# BaseBoard.net
KiCad netlist of a schematic drawn in EAGLE
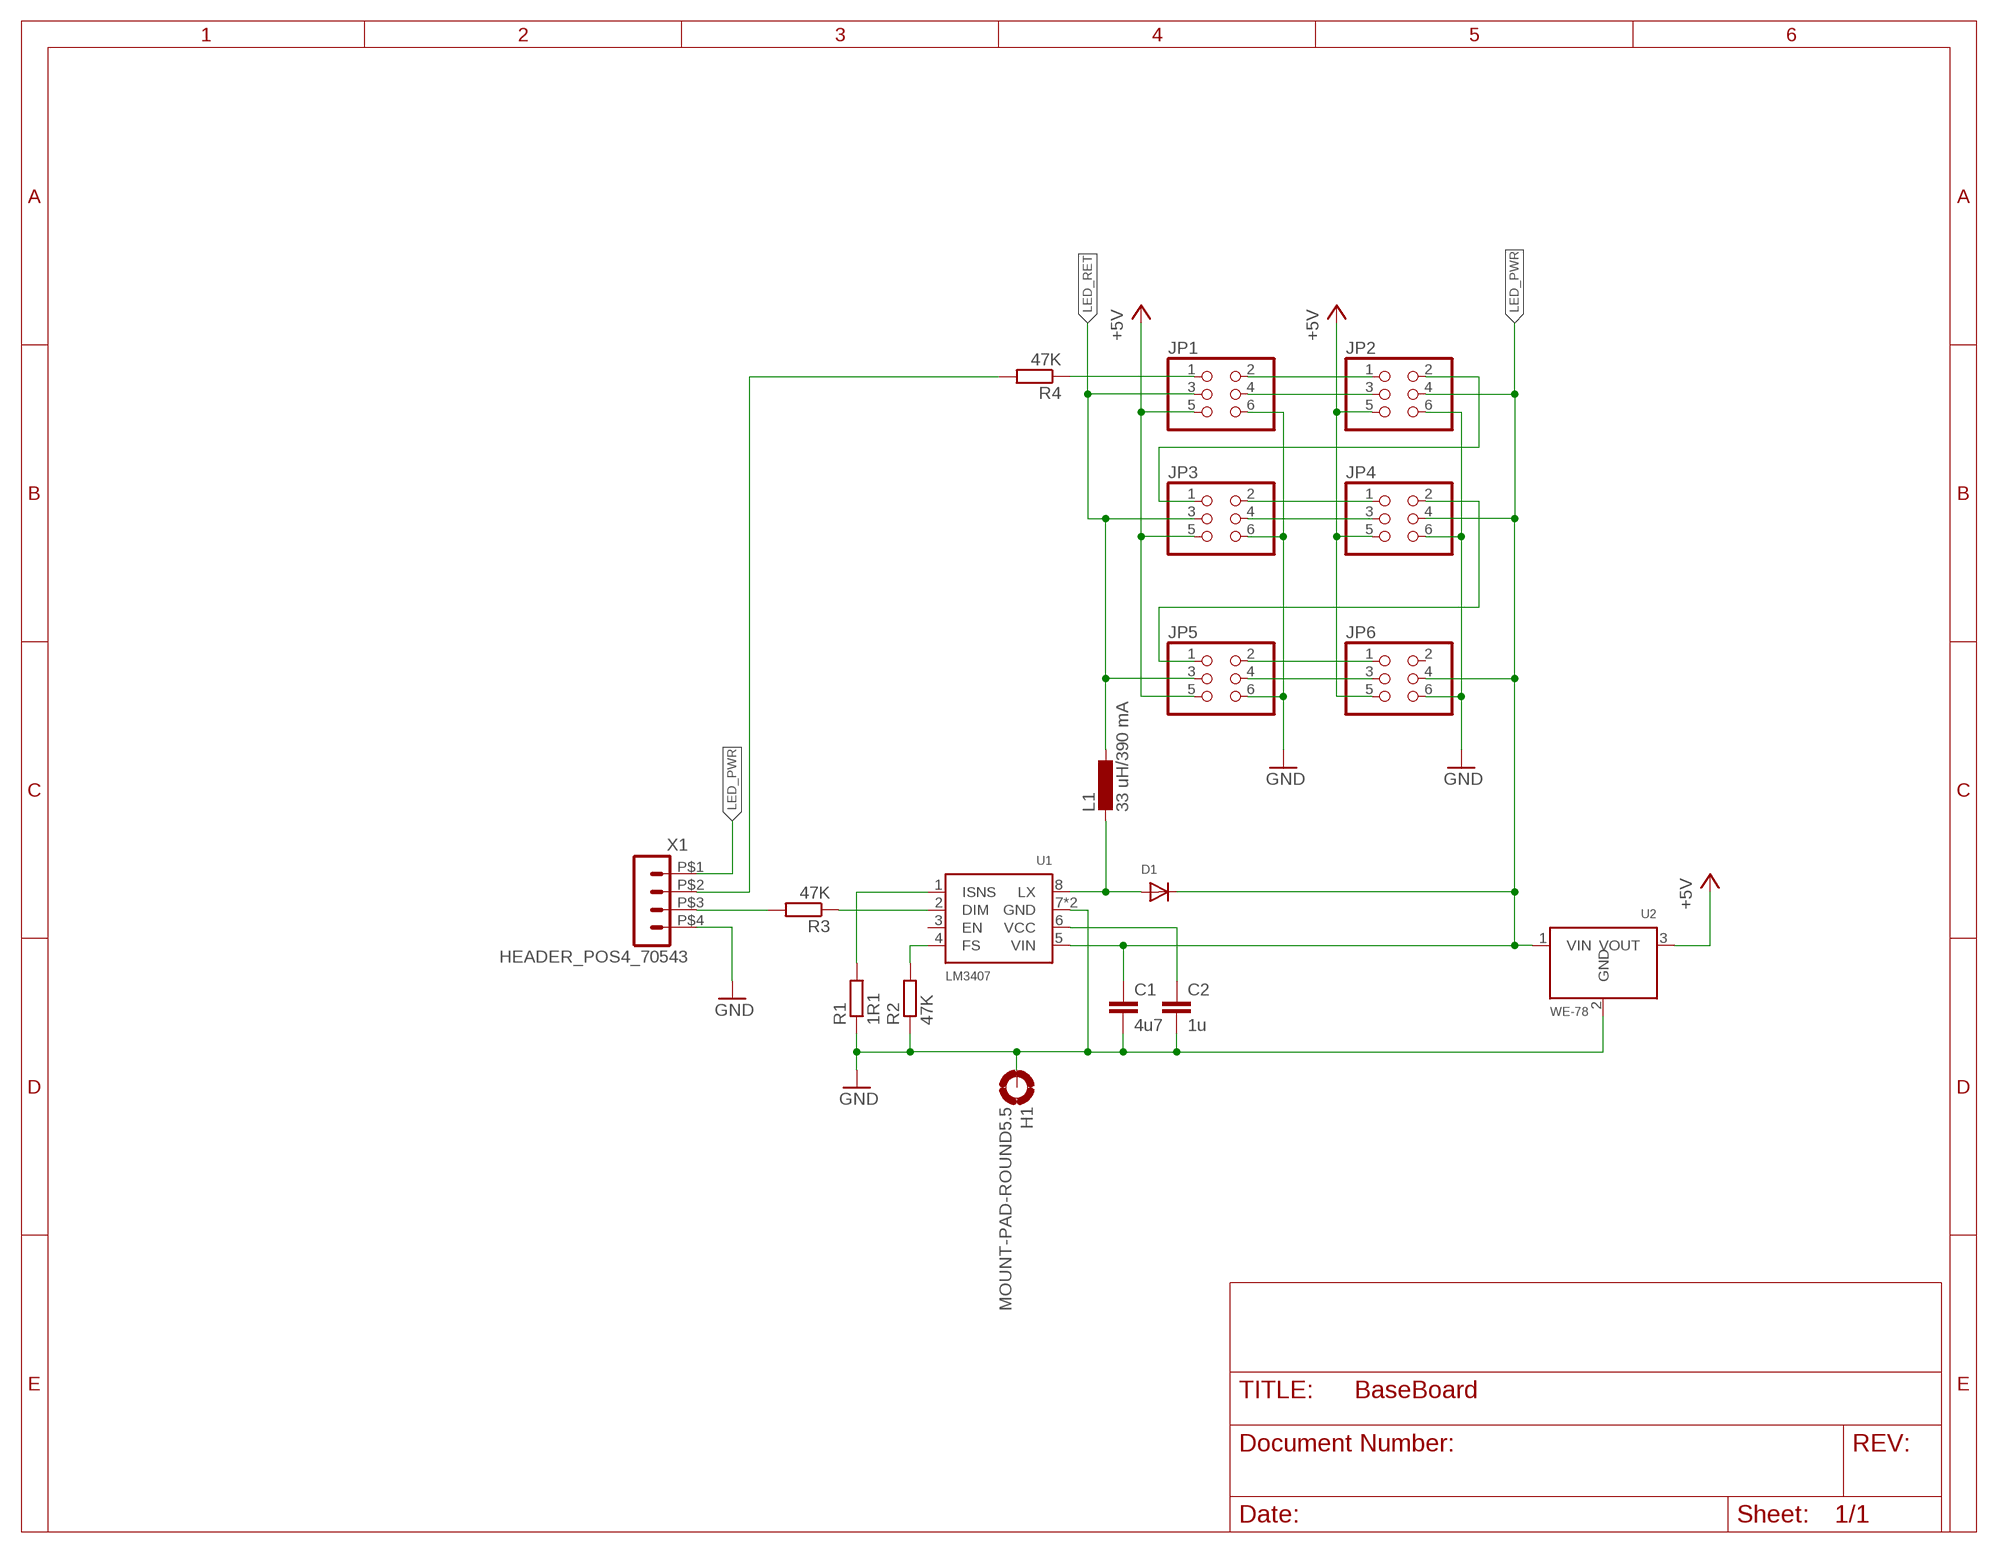
[diagram p0: schematic, sheet 1]

(export (version "E")
  (design (tool "Eeschema 10.0.6"))
  (components
    (comp (ref "C1")
      (value "4u7")
      (footprint "eagle-import:C1206")
      (libsource (lib "eagle-import") (part "C-EUC1206"))
    )
    (comp (ref "C2")
      (value "1u")
      (footprint "eagle-import:C0603")
      (libsource (lib "eagle-import") (part "C-EUC0603"))
    )
    (comp (ref "D1")
      (value "DIODESOD-123")
      (footprint "eagle-import:SOD-123")
      (libsource (lib "eagle-import") (part "DIODESOD-123"))
    )
    (comp (ref "H1")
      (value "MOUNT-PAD-ROUND5.5")
      (footprint "eagle-import:5,5-PAD")
      (libsource (lib "eagle-import") (part "MOUNT-PAD-ROUND5.5"))
    )
    (comp (ref "JP1")
      (value "PINHD-2X3")
      (footprint "eagle-import:2X03")
      (libsource (lib "eagle-import") (part "PINHD-2X3"))
    )
    (comp (ref "JP2")
      (value "PINHD-2X3")
      (footprint "eagle-import:2X03")
      (libsource (lib "eagle-import") (part "PINHD-2X3"))
    )
    (comp (ref "JP3")
      (value "PINHD-2X3")
      (footprint "eagle-import:2X03")
      (libsource (lib "eagle-import") (part "PINHD-2X3"))
    )
    (comp (ref "JP4")
      (value "PINHD-2X3")
      (footprint "eagle-import:2X03")
      (libsource (lib "eagle-import") (part "PINHD-2X3"))
    )
    (comp (ref "JP5")
      (value "PINHD-2X3")
      (footprint "eagle-import:2X03")
      (libsource (lib "eagle-import") (part "PINHD-2X3"))
    )
    (comp (ref "JP6")
      (value "PINHD-2X3")
      (footprint "eagle-import:2X03")
      (libsource (lib "eagle-import") (part "PINHD-2X3"))
    )
    (comp (ref "L1")
      (value "33 uH/390 mA")
      (footprint "eagle-import:C1210")
      (libsource (lib "eagle-import") (part "INDUCTOR-LQH32N"))
    )
    (comp (ref "R1")
      (value "1R1")
      (footprint "eagle-import:R1206")
      (libsource (lib "eagle-import") (part "R-EU_R1206"))
    )
    (comp (ref "R2")
      (value "47K")
      (footprint "eagle-import:R0603")
      (libsource (lib "eagle-import") (part "R-EU_R0603"))
    )
    (comp (ref "R3")
      (value "47K")
      (footprint "eagle-import:R0603")
      (libsource (lib "eagle-import") (part "R-EU_R0603"))
    )
    (comp (ref "R4")
      (value "47K")
      (footprint "eagle-import:R0603")
      (libsource (lib "eagle-import") (part "R-EU_R0603"))
    )
    (comp (ref "U1")
      (value "LM3407")
      (footprint "eagle-import:MSOP8-GND")
      (libsource (lib "eagle-import") (part "LM3407"))
    )
    (comp (ref "U2")
      (value "WE-78")
      (footprint "eagle-import:WE-78")
      (libsource (lib "eagle-import") (part "WE-78"))
    )
    (comp (ref "X1")
      (value "HEADER_POS4_70543")
      (footprint "eagle-import:70543-POS4")
      (libsource (lib "eagle-import") (part "HEADER_POS4_?70543"))
    )
  )
  (nets
    (net (code "1") (name "+5V") (class "Default")
      (node (ref "JP1") (pin "5") (pinfunction "5_5") (pintype "passive"))
      (node (ref "JP2") (pin "5") (pinfunction "5_5") (pintype "passive"))
      (node (ref "JP3") (pin "5") (pinfunction "5_5") (pintype "passive"))
      (node (ref "JP4") (pin "5") (pinfunction "5_5") (pintype "passive"))
      (node (ref "JP5") (pin "5") (pinfunction "5_5") (pintype "passive"))
      (node (ref "JP6") (pin "5") (pinfunction "5_5") (pintype "passive"))
      (node (ref "U2") (pin "3") (pinfunction "VOUT_3") (pintype "bidirectional"))
    )
    (net (code "2") (name "GND") (class "Default")
      (node (ref "C1") (pin "2") (pinfunction "2_2") (pintype "passive"))
      (node (ref "C2") (pin "2") (pinfunction "2_2") (pintype "passive"))
      (node (ref "H1") (pin "B5,5") (pinfunction "MOUNT_B5,5") (pintype "passive"))
      (node (ref "JP1") (pin "6") (pinfunction "6_6") (pintype "passive"))
      (node (ref "JP2") (pin "6") (pinfunction "6_6") (pintype "passive"))
      (node (ref "JP3") (pin "6") (pinfunction "6_6") (pintype "passive"))
      (node (ref "JP4") (pin "6") (pinfunction "6_6") (pintype "passive"))
      (node (ref "JP5") (pin "6") (pinfunction "6_6") (pintype "passive"))
      (node (ref "JP6") (pin "6") (pinfunction "6_6") (pintype "passive"))
      (node (ref "R1") (pin "1") (pinfunction "1_1") (pintype "passive"))
      (node (ref "R2") (pin "1") (pinfunction "1_1") (pintype "passive"))
      (node (ref "U1") (pin "7") (pinfunction "GND_7") (pintype "bidirectional"))
      (node (ref "U1") (pin "THERM") (pinfunction "GND_THERM") (pintype "bidirectional"))
      (node (ref "U2") (pin "2") (pinfunction "GND_2") (pintype "bidirectional"))
      (node (ref "X1") (pin "P$4") (pinfunction "4_P$4") (pintype "passive"))
    )
    (net (code "3") (name "LED_PWR") (class "Default")
      (node (ref "C1") (pin "1") (pinfunction "1_1") (pintype "passive"))
      (node (ref "D1") (pin "C") (pinfunction "C_C") (pintype "passive"))
      (node (ref "JP2") (pin "4") (pinfunction "4_4") (pintype "passive"))
      (node (ref "JP4") (pin "4") (pinfunction "4_4") (pintype "passive"))
      (node (ref "JP6") (pin "4") (pinfunction "4_4") (pintype "passive"))
      (node (ref "U1") (pin "5") (pinfunction "VIN_5") (pintype "bidirectional"))
      (node (ref "U2") (pin "1") (pinfunction "VIN_1") (pintype "bidirectional"))
      (node (ref "X1") (pin "P$1") (pinfunction "1_P$1") (pintype "passive"))
    )
    (net (code "4") (name "LED_RET") (class "Default")
      (node (ref "JP1") (pin "3") (pinfunction "3_3") (pintype "passive"))
      (node (ref "JP3") (pin "3") (pinfunction "3_3") (pintype "passive"))
      (node (ref "JP5") (pin "3") (pinfunction "3_3") (pintype "passive"))
      (node (ref "L1") (pin "1") (pinfunction "1_1") (pintype "passive"))
    )
    (net (code "5") (name "Net-(JP1-Pad1)") (class "Default")
      (node (ref "JP1") (pin "1") (pinfunction "1_1") (pintype "passive"))
      (node (ref "R4") (pin "1") (pinfunction "1_1") (pintype "passive"))
    )
    (net (code "6") (name "Net-(JP1-Pad2)") (class "Default")
      (node (ref "JP1") (pin "2") (pinfunction "2_2") (pintype "passive"))
      (node (ref "JP2") (pin "1") (pinfunction "1_1") (pintype "passive"))
    )
    (net (code "7") (name "Net-(JP1-Pad4)") (class "Default")
      (node (ref "JP1") (pin "4") (pinfunction "4_4") (pintype "passive"))
      (node (ref "JP2") (pin "3") (pinfunction "3_3") (pintype "passive"))
    )
    (net (code "8") (name "Net-(JP2-Pad2)") (class "Default")
      (node (ref "JP2") (pin "2") (pinfunction "2_2") (pintype "passive"))
      (node (ref "JP3") (pin "1") (pinfunction "1_1") (pintype "passive"))
    )
    (net (code "9") (name "Net-(JP3-Pad2)") (class "Default")
      (node (ref "JP3") (pin "2") (pinfunction "2_2") (pintype "passive"))
      (node (ref "JP4") (pin "1") (pinfunction "1_1") (pintype "passive"))
    )
    (net (code "10") (name "Net-(JP3-Pad4)") (class "Default")
      (node (ref "JP3") (pin "4") (pinfunction "4_4") (pintype "passive"))
      (node (ref "JP4") (pin "3") (pinfunction "3_3") (pintype "passive"))
    )
    (net (code "11") (name "Net-(JP4-Pad2)") (class "Default")
      (node (ref "JP4") (pin "2") (pinfunction "2_2") (pintype "passive"))
      (node (ref "JP5") (pin "1") (pinfunction "1_1") (pintype "passive"))
    )
    (net (code "12") (name "Net-(JP5-Pad2)") (class "Default")
      (node (ref "JP5") (pin "2") (pinfunction "2_2") (pintype "passive"))
      (node (ref "JP6") (pin "1") (pinfunction "1_1") (pintype "passive"))
    )
    (net (code "13") (name "Net-(JP5-Pad4)") (class "Default")
      (node (ref "JP5") (pin "4") (pinfunction "4_4") (pintype "passive"))
      (node (ref "JP6") (pin "3") (pinfunction "3_3") (pintype "passive"))
    )
    (net (code "14") (name "Net-(U1-DIM)") (class "Default")
      (node (ref "R3") (pin "1") (pinfunction "1_1") (pintype "passive"))
      (node (ref "U1") (pin "2") (pinfunction "DIM_2") (pintype "bidirectional"))
    )
    (net (code "15") (name "Net-(U1-FS)") (class "Default")
      (node (ref "R2") (pin "2") (pinfunction "2_2") (pintype "passive"))
      (node (ref "U1") (pin "4") (pinfunction "FS_4") (pintype "bidirectional"))
    )
    (net (code "16") (name "Net-(U1-ISNS)") (class "Default")
      (node (ref "R1") (pin "2") (pinfunction "2_2") (pintype "passive"))
      (node (ref "U1") (pin "1") (pinfunction "ISNS_1") (pintype "bidirectional"))
    )
    (net (code "17") (name "Net-(U1-LX)") (class "Default")
      (node (ref "D1") (pin "A") (pinfunction "A_A") (pintype "passive"))
      (node (ref "L1") (pin "2") (pinfunction "2_2") (pintype "passive"))
      (node (ref "U1") (pin "8") (pinfunction "LX_8") (pintype "bidirectional"))
    )
    (net (code "18") (name "Net-(U1-VCC)") (class "Default")
      (node (ref "C2") (pin "1") (pinfunction "1_1") (pintype "passive"))
      (node (ref "U1") (pin "6") (pinfunction "VCC_6") (pintype "bidirectional"))
    )
    (net (code "19") (name "Net-(X1-2)") (class "Default")
      (node (ref "R4") (pin "2") (pinfunction "2_2") (pintype "passive"))
      (node (ref "X1") (pin "P$2") (pinfunction "2_P$2") (pintype "passive"))
    )
    (net (code "20") (name "Net-(X1-3)") (class "Default")
      (node (ref "R3") (pin "2") (pinfunction "2_2") (pintype "passive"))
      (node (ref "X1") (pin "P$3") (pinfunction "3_P$3") (pintype "passive"))
    )
    (net (code "21") (name "unconnected-(JP6-Pad2)") (class "Default")
      (node (ref "JP6") (pin "2") (pinfunction "2_2") (pintype "passive"))
    )
    (net (code "22") (name "unconnected-(U1-EN-Pad3)") (class "Default")
      (node (ref "U1") (pin "3") (pinfunction "EN_3") (pintype "bidirectional"))
    )
  )
)
